# ConnectorsBoard.net
KiCad netlist of a schematic drawn in Altium Designer
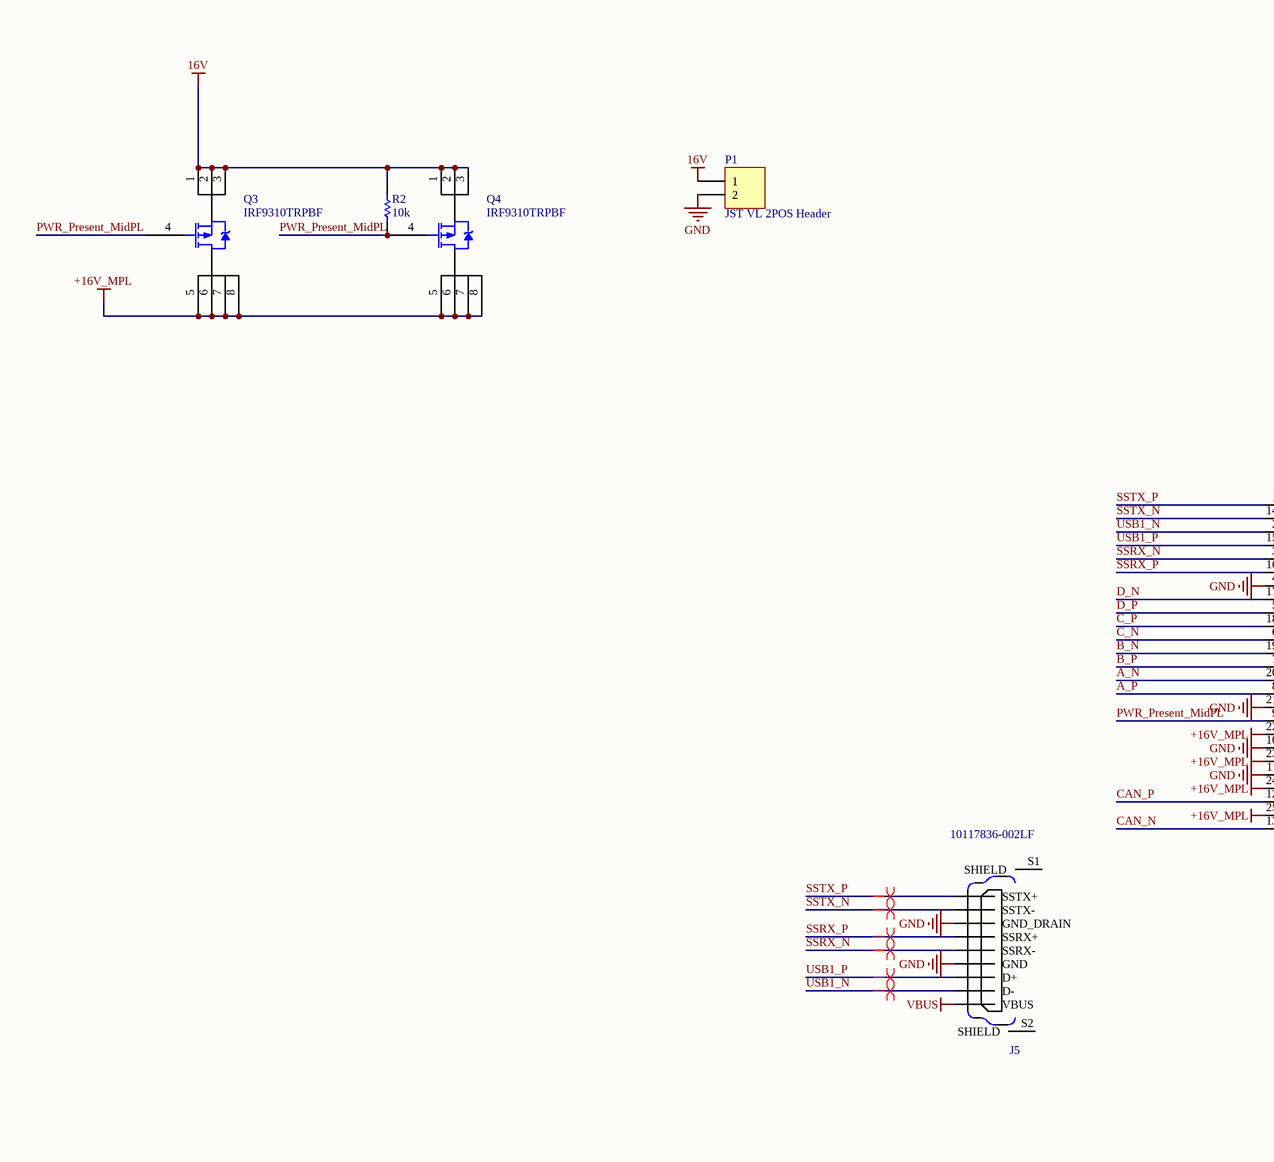
[diagram p0: ConnectorsBoard.SchDoc, left]
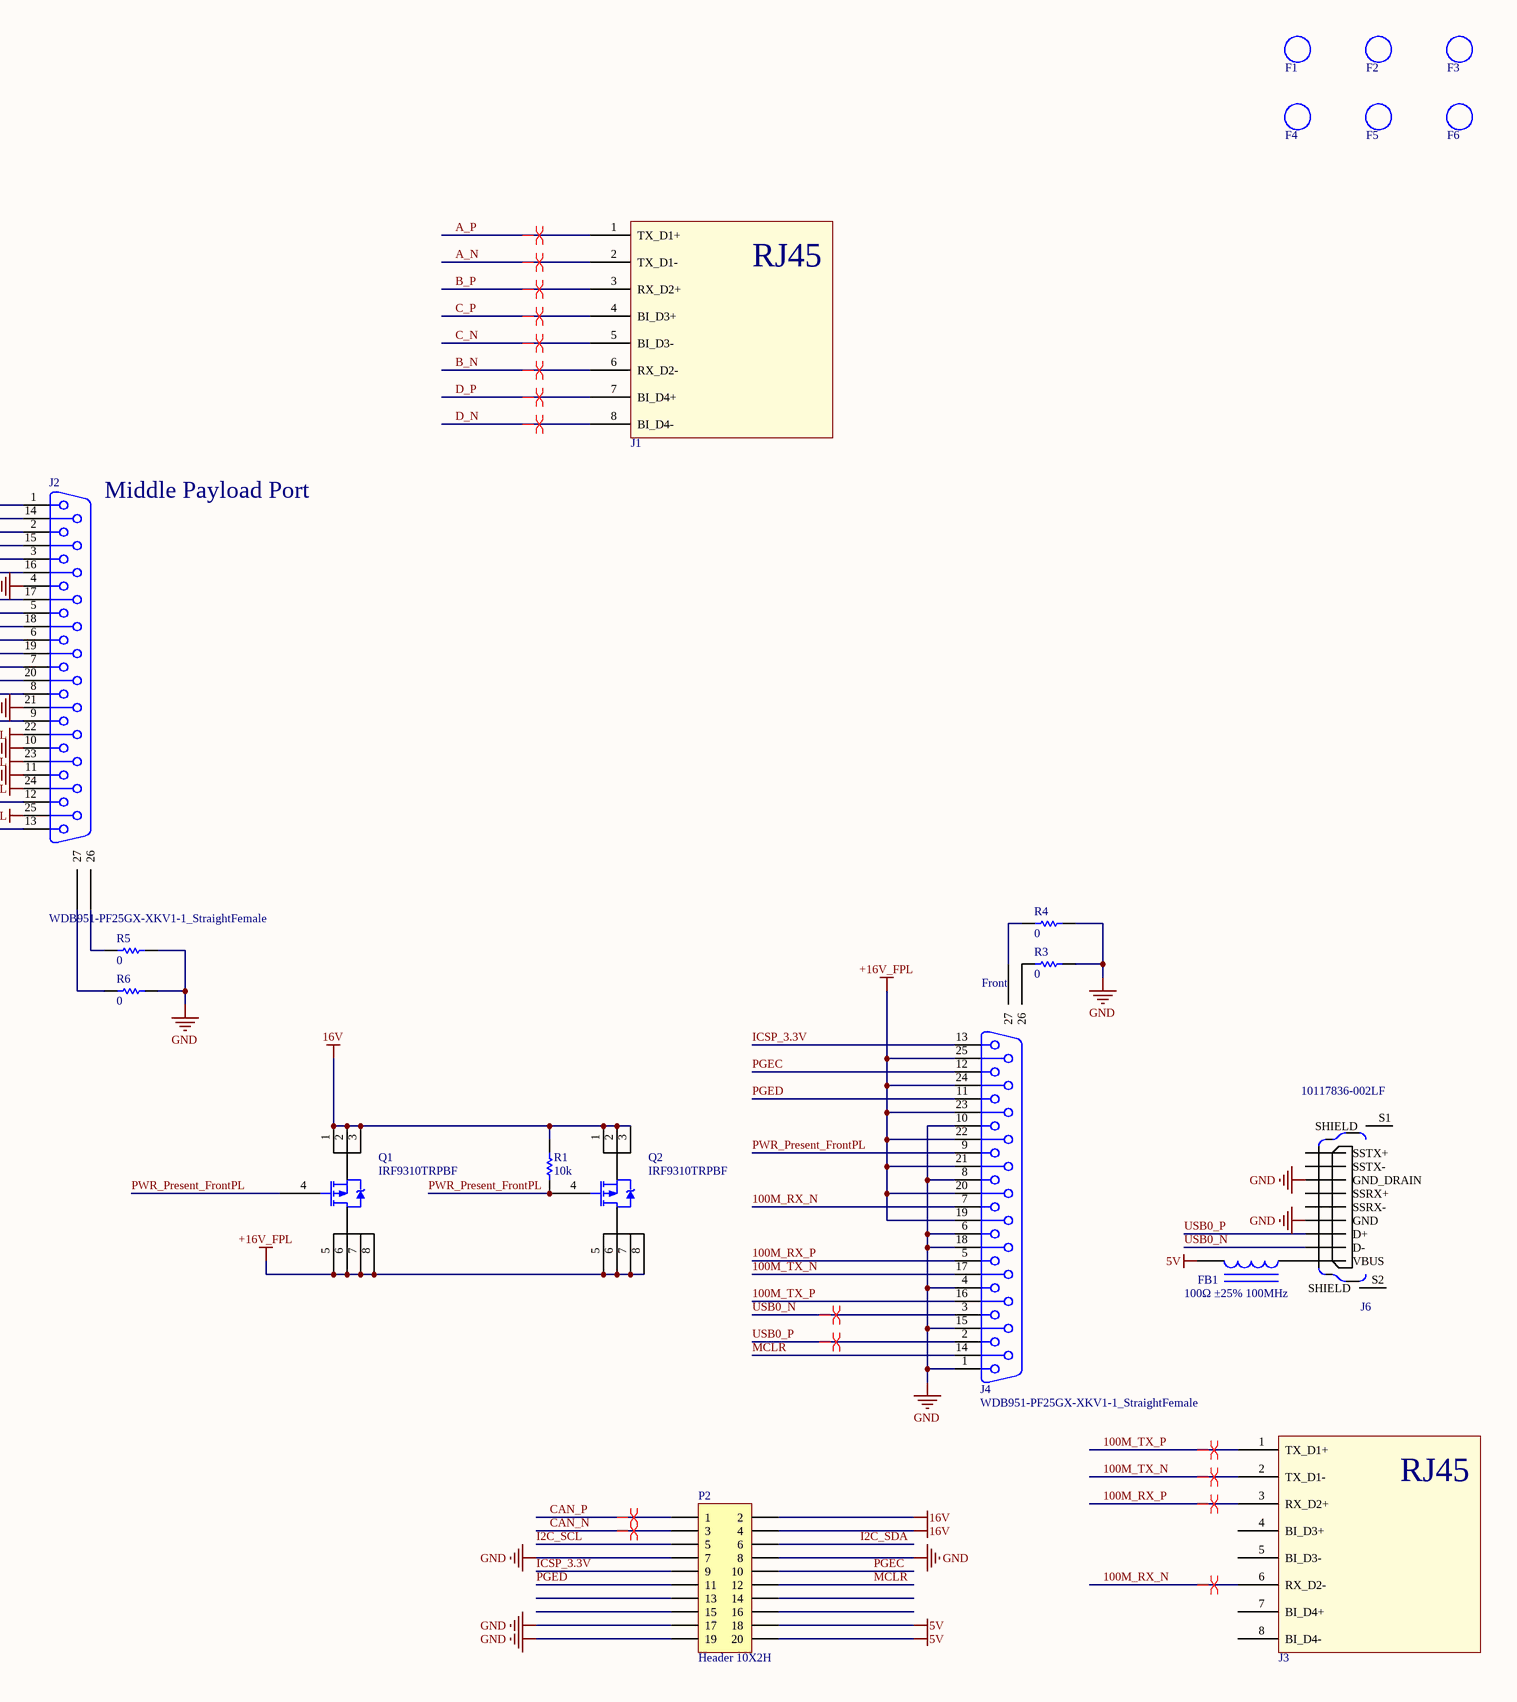
[diagram p1: ConnectorsBoard.SchDoc, right]

(export (version "E")
  (design (tool "Eeschema 10.0.6"))
  (components
    (comp (ref "F1")
      (value "Fiducial, .040\"")
      (footprint "FIDUCIAL, .040\"")
      (libsource (lib "RoboteX") (part "Fiducial"))
    )
    (comp (ref "F2")
      (value "Fiducial, .040\"")
      (footprint "FIDUCIAL, .040\"")
      (libsource (lib "RoboteX") (part "Fiducial"))
    )
    (comp (ref "F3")
      (value "Fiducial, .040\"")
      (footprint "FIDUCIAL, .040\"")
      (libsource (lib "RoboteX") (part "Fiducial"))
    )
    (comp (ref "F4")
      (value "Fiducial, .040\"")
      (footprint "FIDUCIAL, .040\"")
      (libsource (lib "RoboteX") (part "Fiducial"))
    )
    (comp (ref "F5")
      (value "Fiducial, .040\"")
      (footprint "FIDUCIAL, .040\"")
      (libsource (lib "RoboteX") (part "Fiducial"))
    )
    (comp (ref "F6")
      (value "Fiducial, .040\"")
      (footprint "FIDUCIAL, .040\"")
      (libsource (lib "RoboteX") (part "Fiducial"))
    )
    (comp (ref "FB1")
      (value "100Ω ±25% 100MHz")
      (footprint "0805_L")
      (description "贴片磁珠")
      (libsource (lib "Miscellaneous Devices LC") (part "0805 100Ω 25% 100MHz"))
    )
    (comp (ref "J1")
      (value "Jack Modular Connector 8p8c (RJ45, Ethernet) Vertical Unshielded Cat3")
      (footprint "RJ45-5556416-1")
      (description "RJ45 connector 180 degrees")
      (fields (field (name "PART NUMBER") "5556416-1") (field (name "MANUFACTURER") "TE"))
      (libsource (lib "RoboteX") (part "RJ45_180"))
    )
    (comp (ref "J2")
      (value "WDB951-PF25GX-XKV1-1_StraightFemale")
      (footprint "WDB951-PF25GX-XKV1-1_StraightFemale")
      (libsource (lib "RoboteX") (part "DSUB-25_Female_Board_Locks"))
    )
    (comp (ref "J3")
      (value "Jack Modular Connector 8p8c (RJ45, Ethernet) Vertical Unshielded Cat3")
      (footprint "RJ45-5556416-1")
      (description "RJ45 connector 180 degrees")
      (fields (field (name "PART NUMBER") "5556416-1") (field (name "MANUFACTURER") "TE"))
      (libsource (lib "RoboteX") (part "RJ45_180"))
    )
    (comp (ref "J4")
      (value "WDB951-PF25GX-XKV1-1_StraightFemale")
      (footprint "WDB951-PF25GX-XKV1-1_StraightFemale")
      (libsource (lib "RoboteX") (part "DSUB-25_Female_Board_Locks"))
    )
    (comp (ref "J5")
      (value "10117836-002LF")
      (footprint "AMPHENOL_10117836-002LF_10117836-002LF(Primary)")
      (description "Usb, 3.0 Type A, Receptacle, SMT")
      (fields
        (field (name "MANUFACTURER") "Amphenol FCI")
        (field (name "DIGI-KEY_PART_NUMBER") "609-4660-ND")
      )
      (libsource (lib "lib") (part "10117836-002LF"))
    )
    (comp (ref "J6")
      (value "10117836-002LF")
      (footprint "AMPHENOL_10117836-002LF_10117836-002LF(Primary)")
      (description "Usb, 3.0 Type A, Receptacle, SMT")
      (fields
        (field (name "MANUFACTURER") "Amphenol FCI")
        (field (name "DIGI-KEY_PART_NUMBER") "609-4660-ND")
      )
      (libsource (lib "lib") (part "10117836-002LF"))
    )
    (comp (ref "P1")
      (value "JST VL 2POS Header")
      (footprint "JST-VL-2POS")
      (description "CONN HEADER 2POS VL SERIES TIN")
      (fields
        (field (name "MANUFACTURER") "JST Sales America Inc")
        (field (name "MANUFACTURER PART NUMBER") "B02P-VL")
      )
      (libsource (lib "RoboteX") (part "Header 2 POS"))
    )
    (comp (ref "P2")
      (value "Header 10X2H")
      (footprint "HDR_2X10")
      (description "Header, 10-Pin, Dual row, Right Angle")
      (fields
        (field (name "MANUFACTURER PART NUMBER") "AWHW 10G-0202-T")
        (field (name "MANUFACTURER") "Assmann WSW Components")
        (field (name "PUBLISHER") "Altium Limited")
      )
      (libsource (lib "Miscellaneous Connectors") (part "Header 10X2H"))
    )
    (comp (ref "Q1")
      (value "IRF9310TRPBF")
      (footprint "SOIC-SN8_M")
      (description "MOSFET P-CH 30V 20A 8-SOIC")
      (fields (field (name "MANUFACTURER") "International Rectifier"))
      (libsource (lib "RoboteX") (part "MOSFET_P_8_PADS"))
    )
    (comp (ref "Q2")
      (value "IRF9310TRPBF")
      (footprint "SOIC-SN8_M")
      (description "MOSFET P-CH 30V 20A 8-SOIC")
      (fields (field (name "MANUFACTURER") "International Rectifier"))
      (libsource (lib "RoboteX") (part "MOSFET_P_8_PADS"))
    )
    (comp (ref "Q3")
      (value "IRF9310TRPBF")
      (footprint "SOIC-SN8_M")
      (description "MOSFET P-CH 30V 20A 8-SOIC")
      (fields (field (name "MANUFACTURER") "International Rectifier"))
      (libsource (lib "RoboteX") (part "MOSFET_P_8_PADS"))
    )
    (comp (ref "Q4")
      (value "IRF9310TRPBF")
      (footprint "SOIC-SN8_M")
      (description "MOSFET P-CH 30V 20A 8-SOIC")
      (fields (field (name "MANUFACTURER") "International Rectifier"))
      (libsource (lib "RoboteX") (part "MOSFET_P_8_PADS"))
    )
    (comp (ref "R1")
      (value "10k")
      (footprint "RES0805N")
      (description "RES 10.0K OHM 1/8W 1% 0805 SMD")
      (fields
        (field (name "MANUFACTURER") "Panasonic - ECG")
        (field (name "MANUFACTURER PART NUMBER") "ERJ-6ENF1002V")
      )
      (libsource (lib "RoboteX") (part "Res"))
    )
    (comp (ref "R2")
      (value "10k")
      (footprint "RES0805N")
      (description "RES 10.0K OHM 1/8W 1% 0805 SMD")
      (fields
        (field (name "MANUFACTURER") "Panasonic - ECG")
        (field (name "MANUFACTURER PART NUMBER") "ERJ-6ENF1002V")
      )
      (libsource (lib "RoboteX") (part "Res"))
    )
    (comp (ref "R3")
      (value "0")
      (footprint "RES0805N")
      (description "RES 0.0 OHM 1/8W 0805 SMD")
      (fields
        (field (name "MANUFACTURER") "Stackpole Electronics Inc")
        (field (name "MANUFACTURER PART NUMBER") "RMCF0805ZT0R00")
      )
      (libsource (lib "RoboteX") (part "Res"))
    )
    (comp (ref "R4")
      (value "0")
      (footprint "RES0805N")
      (description "RES 0.0 OHM 1/8W 0805 SMD")
      (fields
        (field (name "MANUFACTURER") "Stackpole Electronics Inc")
        (field (name "MANUFACTURER PART NUMBER") "RMCF0805ZT0R00")
      )
      (libsource (lib "RoboteX") (part "Res"))
    )
    (comp (ref "R5")
      (value "0")
      (footprint "RES0805N")
      (description "RES 0.0 OHM 1/8W 0805 SMD")
      (fields
        (field (name "MANUFACTURER") "Stackpole Electronics Inc")
        (field (name "MANUFACTURER PART NUMBER") "RMCF0805ZT0R00")
      )
      (libsource (lib "RoboteX") (part "Res"))
    )
    (comp (ref "R6")
      (value "0")
      (footprint "RES0805N")
      (description "RES 0.0 OHM 1/8W 0805 SMD")
      (fields
        (field (name "MANUFACTURER") "Stackpole Electronics Inc")
        (field (name "MANUFACTURER PART NUMBER") "RMCF0805ZT0R00")
      )
      (libsource (lib "RoboteX") (part "Res"))
    )
  )
  (nets
    (net (code "1") (name "+16V_FPL") (class "Default")
      (node (ref "J4") (pin "19") (pinfunction "19_19") (pintype "passive"))
      (node (ref "J4") (pin "20") (pinfunction "20_20") (pintype "passive"))
      (node (ref "J4") (pin "21") (pinfunction "21_21") (pintype "passive"))
      (node (ref "J4") (pin "22") (pinfunction "22_22") (pintype "passive"))
      (node (ref "J4") (pin "23") (pinfunction "23_23") (pintype "passive"))
      (node (ref "J4") (pin "24") (pinfunction "24_24") (pintype "passive"))
      (node (ref "J4") (pin "25") (pinfunction "25_25") (pintype "passive"))
      (node (ref "Q1") (pin "5") (pinfunction "5_5") (pintype "passive"))
      (node (ref "Q1") (pin "6") (pinfunction "6_6") (pintype "passive"))
      (node (ref "Q1") (pin "7") (pinfunction "7_7") (pintype "passive"))
      (node (ref "Q1") (pin "8") (pinfunction "8_8") (pintype "passive"))
      (node (ref "Q2") (pin "5") (pinfunction "5_5") (pintype "passive"))
      (node (ref "Q2") (pin "6") (pinfunction "6_6") (pintype "passive"))
      (node (ref "Q2") (pin "7") (pinfunction "7_7") (pintype "passive"))
      (node (ref "Q2") (pin "8") (pinfunction "8_8") (pintype "passive"))
    )
    (net (code "2") (name "+16V_MPL") (class "Default")
      (node (ref "J2") (pin "22") (pinfunction "22_22") (pintype "passive"))
      (node (ref "J2") (pin "23") (pinfunction "23_23") (pintype "passive"))
      (node (ref "J2") (pin "24") (pinfunction "24_24") (pintype "passive"))
      (node (ref "J2") (pin "25") (pinfunction "25_25") (pintype "passive"))
      (node (ref "Q3") (pin "5") (pinfunction "5_5") (pintype "passive"))
      (node (ref "Q3") (pin "6") (pinfunction "6_6") (pintype "passive"))
      (node (ref "Q3") (pin "7") (pinfunction "7_7") (pintype "passive"))
      (node (ref "Q3") (pin "8") (pinfunction "8_8") (pintype "passive"))
      (node (ref "Q4") (pin "5") (pinfunction "5_5") (pintype "passive"))
      (node (ref "Q4") (pin "6") (pinfunction "6_6") (pintype "passive"))
      (node (ref "Q4") (pin "7") (pinfunction "7_7") (pintype "passive"))
      (node (ref "Q4") (pin "8") (pinfunction "8_8") (pintype "passive"))
    )
    (net (code "3") (name "/100M_RX_N") (class "Default")
      (node (ref "J3") (pin "6") (pinfunction "RX_D2-_6") (pintype "passive"))
      (node (ref "J4") (pin "7") (pinfunction "7_7") (pintype "passive"))
    )
    (net (code "4") (name "/100M_RX_P") (class "Default")
      (node (ref "J3") (pin "3") (pinfunction "RX_D2+_3") (pintype "passive"))
      (node (ref "J4") (pin "5") (pinfunction "5_5") (pintype "passive"))
    )
    (net (code "5") (name "/100M_TX_N") (class "Default")
      (node (ref "J3") (pin "2") (pinfunction "TX_D1-_2") (pintype "passive"))
      (node (ref "J4") (pin "17") (pinfunction "17_17") (pintype "passive"))
    )
    (net (code "6") (name "/100M_TX_P") (class "Default")
      (node (ref "J3") (pin "1") (pinfunction "TX_D1+_1") (pintype "passive"))
      (node (ref "J4") (pin "16") (pinfunction "16_16") (pintype "passive"))
    )
    (net (code "7") (name "/A_N") (class "Default")
      (node (ref "J1") (pin "2") (pinfunction "TX_D1-_2") (pintype "passive"))
      (node (ref "J2") (pin "20") (pinfunction "20_20") (pintype "passive"))
    )
    (net (code "8") (name "/A_P") (class "Default")
      (node (ref "J1") (pin "1") (pinfunction "TX_D1+_1") (pintype "passive"))
      (node (ref "J2") (pin "8") (pinfunction "8_8") (pintype "passive"))
    )
    (net (code "9") (name "/B_N") (class "Default")
      (node (ref "J1") (pin "6") (pinfunction "RX_D2-_6") (pintype "passive"))
      (node (ref "J2") (pin "19") (pinfunction "19_19") (pintype "passive"))
    )
    (net (code "10") (name "/B_P") (class "Default")
      (node (ref "J1") (pin "3") (pinfunction "RX_D2+_3") (pintype "passive"))
      (node (ref "J2") (pin "7") (pinfunction "7_7") (pintype "passive"))
    )
    (net (code "11") (name "/CAN_N") (class "Default")
      (node (ref "J2") (pin "13") (pinfunction "13_13") (pintype "passive"))
      (node (ref "P2") (pin "3") (pinfunction "3_3") (pintype "passive"))
    )
    (net (code "12") (name "/CAN_P") (class "Default")
      (node (ref "J2") (pin "12") (pinfunction "12_12") (pintype "passive"))
      (node (ref "P2") (pin "1") (pinfunction "1_1") (pintype "passive"))
    )
    (net (code "13") (name "/C_N") (class "Default")
      (node (ref "J1") (pin "5") (pinfunction "BI_D3-_5") (pintype "passive"))
      (node (ref "J2") (pin "6") (pinfunction "6_6") (pintype "passive"))
    )
    (net (code "14") (name "/C_P") (class "Default")
      (node (ref "J1") (pin "4") (pinfunction "BI_D3+_4") (pintype "passive"))
      (node (ref "J2") (pin "18") (pinfunction "18_18") (pintype "passive"))
    )
    (net (code "15") (name "/D_N") (class "Default")
      (node (ref "J1") (pin "8") (pinfunction "BI_D4-_8") (pintype "passive"))
      (node (ref "J2") (pin "17") (pinfunction "17_17") (pintype "passive"))
    )
    (net (code "16") (name "/D_P") (class "Default")
      (node (ref "J1") (pin "7") (pinfunction "BI_D4+_7") (pintype "passive"))
      (node (ref "J2") (pin "5") (pinfunction "5_5") (pintype "passive"))
    )
    (net (code "17") (name "/I2C_SCL") (class "Default")
      (node (ref "P2") (pin "5") (pinfunction "5_5") (pintype "passive"))
    )
    (net (code "18") (name "/I2C_SDA") (class "Default")
      (node (ref "P2") (pin "6") (pinfunction "6_6") (pintype "passive"))
    )
    (net (code "19") (name "/ICSP_3.3V") (class "Default")
      (node (ref "J4") (pin "13") (pinfunction "13_13") (pintype "passive"))
      (node (ref "P2") (pin "9") (pinfunction "9_9") (pintype "passive"))
    )
    (net (code "20") (name "/MCLR") (class "Default")
      (node (ref "J4") (pin "14") (pinfunction "14_14") (pintype "passive"))
      (node (ref "P2") (pin "12") (pinfunction "12_12") (pintype "passive"))
    )
    (net (code "21") (name "/PGEC") (class "Default")
      (node (ref "J4") (pin "12") (pinfunction "12_12") (pintype "passive"))
      (node (ref "P2") (pin "10") (pinfunction "10_10") (pintype "passive"))
    )
    (net (code "22") (name "/PGED") (class "Default")
      (node (ref "J4") (pin "11") (pinfunction "11_11") (pintype "passive"))
      (node (ref "P2") (pin "11") (pinfunction "11_11") (pintype "passive"))
    )
    (net (code "23") (name "/PWR_Present_FrontPL") (class "Default")
      (node (ref "J4") (pin "9") (pinfunction "9_9") (pintype "passive"))
      (node (ref "Q1") (pin "4") (pinfunction "4_4") (pintype "passive"))
      (node (ref "Q2") (pin "4") (pinfunction "4_4") (pintype "passive"))
      (node (ref "R1") (pin "1") (pinfunction "1_1") (pintype "passive"))
    )
    (net (code "24") (name "/PWR_Present_MidPL") (class "Default")
      (node (ref "J2") (pin "9") (pinfunction "9_9") (pintype "passive"))
      (node (ref "Q3") (pin "4") (pinfunction "4_4") (pintype "passive"))
      (node (ref "Q4") (pin "4") (pinfunction "4_4") (pintype "passive"))
      (node (ref "R2") (pin "1") (pinfunction "1_1") (pintype "passive"))
    )
    (net (code "25") (name "/SSRX_N") (class "Default")
      (node (ref "J2") (pin "3") (pinfunction "3_3") (pintype "passive"))
      (node (ref "J5") (pin "5") (pinfunction "SSRX-_5") (pintype "passive"))
    )
    (net (code "26") (name "/SSRX_P") (class "Default")
      (node (ref "J2") (pin "16") (pinfunction "16_16") (pintype "passive"))
      (node (ref "J5") (pin "6") (pinfunction "SSRX+_6") (pintype "passive"))
    )
    (net (code "27") (name "/SSTX_N") (class "Default")
      (node (ref "J2") (pin "14") (pinfunction "14_14") (pintype "passive"))
      (node (ref "J5") (pin "8") (pinfunction "SSTX-_8") (pintype "passive"))
    )
    (net (code "28") (name "/SSTX_P") (class "Default")
      (node (ref "J2") (pin "1") (pinfunction "1_1") (pintype "passive"))
      (node (ref "J5") (pin "9") (pinfunction "SSTX+_9") (pintype "passive"))
    )
    (net (code "29") (name "/USB0_N") (class "Default")
      (node (ref "J4") (pin "3") (pinfunction "3_3") (pintype "passive"))
      (node (ref "J6") (pin "2") (pinfunction "D-_2") (pintype "passive"))
    )
    (net (code "30") (name "/USB0_P") (class "Default")
      (node (ref "J4") (pin "2") (pinfunction "2_2") (pintype "passive"))
      (node (ref "J6") (pin "3") (pinfunction "D+_3") (pintype "passive"))
    )
    (net (code "31") (name "/USB1_N") (class "Default")
      (node (ref "J2") (pin "2") (pinfunction "2_2") (pintype "passive"))
      (node (ref "J5") (pin "2") (pinfunction "D-_2") (pintype "passive"))
    )
    (net (code "32") (name "/USB1_P") (class "Default")
      (node (ref "J2") (pin "15") (pinfunction "15_15") (pintype "passive"))
      (node (ref "J5") (pin "3") (pinfunction "D+_3") (pintype "passive"))
    )
    (net (code "33") (name "5V") (class "Default")
      (node (ref "FB1") (pin "2") (pinfunction "2_2") (pintype "passive"))
      (node (ref "P2") (pin "18") (pinfunction "18_18") (pintype "passive"))
      (node (ref "P2") (pin "20") (pinfunction "20_20") (pintype "passive"))
    )
    (net (code "34") (name "16V") (class "Default")
      (node (ref "P1") (pin "1") (pinfunction "1_1") (pintype "passive"))
      (node (ref "P2") (pin "2") (pinfunction "2_2") (pintype "passive"))
      (node (ref "P2") (pin "4") (pinfunction "4_4") (pintype "passive"))
      (node (ref "Q1") (pin "1") (pinfunction "G_1") (pintype "passive"))
      (node (ref "Q1") (pin "2") (pinfunction "D_2") (pintype "passive"))
      (node (ref "Q1") (pin "3") (pinfunction "S_3") (pintype "passive"))
      (node (ref "Q2") (pin "1") (pinfunction "G_1") (pintype "passive"))
      (node (ref "Q2") (pin "2") (pinfunction "D_2") (pintype "passive"))
      (node (ref "Q2") (pin "3") (pinfunction "S_3") (pintype "passive"))
      (node (ref "Q3") (pin "1") (pinfunction "G_1") (pintype "passive"))
      (node (ref "Q3") (pin "2") (pinfunction "D_2") (pintype "passive"))
      (node (ref "Q3") (pin "3") (pinfunction "S_3") (pintype "passive"))
      (node (ref "Q4") (pin "1") (pinfunction "G_1") (pintype "passive"))
      (node (ref "Q4") (pin "2") (pinfunction "D_2") (pintype "passive"))
      (node (ref "Q4") (pin "3") (pinfunction "S_3") (pintype "passive"))
      (node (ref "R1") (pin "2") (pinfunction "2_2") (pintype "passive"))
      (node (ref "R2") (pin "2") (pinfunction "2_2") (pintype "passive"))
    )
    (net (code "35") (name "GND") (class "Default")
      (node (ref "J2") (pin "10") (pinfunction "10_10") (pintype "passive"))
      (node (ref "J2") (pin "11") (pinfunction "11_11") (pintype "passive"))
      (node (ref "J2") (pin "21") (pinfunction "21_21") (pintype "passive"))
      (node (ref "J2") (pin "4") (pinfunction "4_4") (pintype "passive"))
      (node (ref "J4") (pin "1") (pinfunction "1_1") (pintype "passive"))
      (node (ref "J4") (pin "10") (pinfunction "10_10") (pintype "passive"))
      (node (ref "J4") (pin "15") (pinfunction "15_15") (pintype "passive"))
      (node (ref "J4") (pin "18") (pinfunction "18_18") (pintype "passive"))
      (node (ref "J4") (pin "4") (pinfunction "4_4") (pintype "passive"))
      (node (ref "J4") (pin "6") (pinfunction "6_6") (pintype "passive"))
      (node (ref "J4") (pin "8") (pinfunction "8_8") (pintype "passive"))
      (node (ref "J5") (pin "4") (pinfunction "GND_4") (pintype "passive"))
      (node (ref "J5") (pin "7") (pinfunction "GND_DRAIN_7") (pintype "passive"))
      (node (ref "J6") (pin "4") (pinfunction "GND_4") (pintype "passive"))
      (node (ref "J6") (pin "7") (pinfunction "GND_DRAIN_7") (pintype "passive"))
      (node (ref "P1") (pin "2") (pinfunction "2_2") (pintype "passive"))
      (node (ref "P2") (pin "17") (pinfunction "17_17") (pintype "passive"))
      (node (ref "P2") (pin "19") (pinfunction "19_19") (pintype "passive"))
      (node (ref "P2") (pin "7") (pinfunction "7_7") (pintype "passive"))
      (node (ref "P2") (pin "8") (pinfunction "8_8") (pintype "passive"))
      (node (ref "R3") (pin "2") (pinfunction "2_2") (pintype "passive"))
      (node (ref "R4") (pin "2") (pinfunction "2_2") (pintype "passive"))
      (node (ref "R5") (pin "2") (pinfunction "2_2") (pintype "passive"))
      (node (ref "R6") (pin "2") (pinfunction "2_2") (pintype "passive"))
    )
    (net (code "36") (name "Net-(J2-Pad26)") (class "Default")
      (node (ref "J2") (pin "26") (pinfunction "26_26") (pintype "passive"))
      (node (ref "R5") (pin "1") (pinfunction "1_1") (pintype "passive"))
    )
    (net (code "37") (name "Net-(J2-Pad27)") (class "Default")
      (node (ref "J2") (pin "27") (pinfunction "27_27") (pintype "passive"))
      (node (ref "R6") (pin "1") (pinfunction "1_1") (pintype "passive"))
    )
    (net (code "38") (name "Net-(J4-Pad26)") (class "Default")
      (node (ref "J4") (pin "26") (pinfunction "26_26") (pintype "passive"))
      (node (ref "R3") (pin "1") (pinfunction "1_1") (pintype "passive"))
    )
    (net (code "39") (name "Net-(J4-Pad27)") (class "Default")
      (node (ref "J4") (pin "27") (pinfunction "27_27") (pintype "passive"))
      (node (ref "R4") (pin "1") (pinfunction "1_1") (pintype "passive"))
    )
    (net (code "40") (name "Net-(J6-VBUS)") (class "Default")
      (node (ref "FB1") (pin "1") (pinfunction "1_1") (pintype "passive"))
      (node (ref "J6") (pin "1") (pinfunction "VBUS_1") (pintype "passive"))
    )
    (net (code "41") (name "VBUS") (class "Default")
      (node (ref "J5") (pin "1") (pinfunction "VBUS_1") (pintype "passive"))
    )
    (net (code "42") (name "unconnected-(J3-BI_D3+-Pad4)") (class "Default")
      (node (ref "J3") (pin "4") (pinfunction "BI_D3+_4") (pintype "passive"))
    )
    (net (code "43") (name "unconnected-(J3-BI_D3--Pad5)") (class "Default")
      (node (ref "J3") (pin "5") (pinfunction "BI_D3-_5") (pintype "passive"))
    )
    (net (code "44") (name "unconnected-(J3-BI_D4+-Pad7)") (class "Default")
      (node (ref "J3") (pin "7") (pinfunction "BI_D4+_7") (pintype "passive"))
    )
    (net (code "45") (name "unconnected-(J3-BI_D4--Pad8)") (class "Default")
      (node (ref "J3") (pin "8") (pinfunction "BI_D4-_8") (pintype "passive"))
    )
    (net (code "46") (name "unconnected-(J5-SHIELD-PadS1)") (class "Default")
      (node (ref "J5") (pin "S1") (pinfunction "SHIELD_S1") (pintype "passive"))
    )
    (net (code "47") (name "unconnected-(J5-SHIELD-PadS2)") (class "Default")
      (node (ref "J5") (pin "S2") (pinfunction "SHIELD_S2") (pintype "passive"))
    )
    (net (code "48") (name "unconnected-(J6-SHIELD-PadS1)") (class "Default")
      (node (ref "J6") (pin "S1") (pinfunction "SHIELD_S1") (pintype "passive"))
    )
    (net (code "49") (name "unconnected-(J6-SHIELD-PadS2)") (class "Default")
      (node (ref "J6") (pin "S2") (pinfunction "SHIELD_S2") (pintype "passive"))
    )
    (net (code "50") (name "unconnected-(J6-SSRX+-Pad6)") (class "Default")
      (node (ref "J6") (pin "6") (pinfunction "SSRX+_6") (pintype "passive"))
    )
    (net (code "51") (name "unconnected-(J6-SSRX--Pad5)") (class "Default")
      (node (ref "J6") (pin "5") (pinfunction "SSRX-_5") (pintype "passive"))
    )
    (net (code "52") (name "unconnected-(J6-SSTX+-Pad9)") (class "Default")
      (node (ref "J6") (pin "9") (pinfunction "SSTX+_9") (pintype "passive"))
    )
    (net (code "53") (name "unconnected-(J6-SSTX--Pad8)") (class "Default")
      (node (ref "J6") (pin "8") (pinfunction "SSTX-_8") (pintype "passive"))
    )
    (net (code "54") (name "unconnected-(P2-Pad13)") (class "Default")
      (node (ref "P2") (pin "13") (pinfunction "13_13") (pintype "passive"))
    )
    (net (code "55") (name "unconnected-(P2-Pad14)") (class "Default")
      (node (ref "P2") (pin "14") (pinfunction "14_14") (pintype "passive"))
    )
    (net (code "56") (name "unconnected-(P2-Pad15)") (class "Default")
      (node (ref "P2") (pin "15") (pinfunction "15_15") (pintype "passive"))
    )
    (net (code "57") (name "unconnected-(P2-Pad16)") (class "Default")
      (node (ref "P2") (pin "16") (pinfunction "16_16") (pintype "passive"))
    )
  )
)
